# TFTLCD.net
KiCad netlist of a schematic drawn in EAGLE
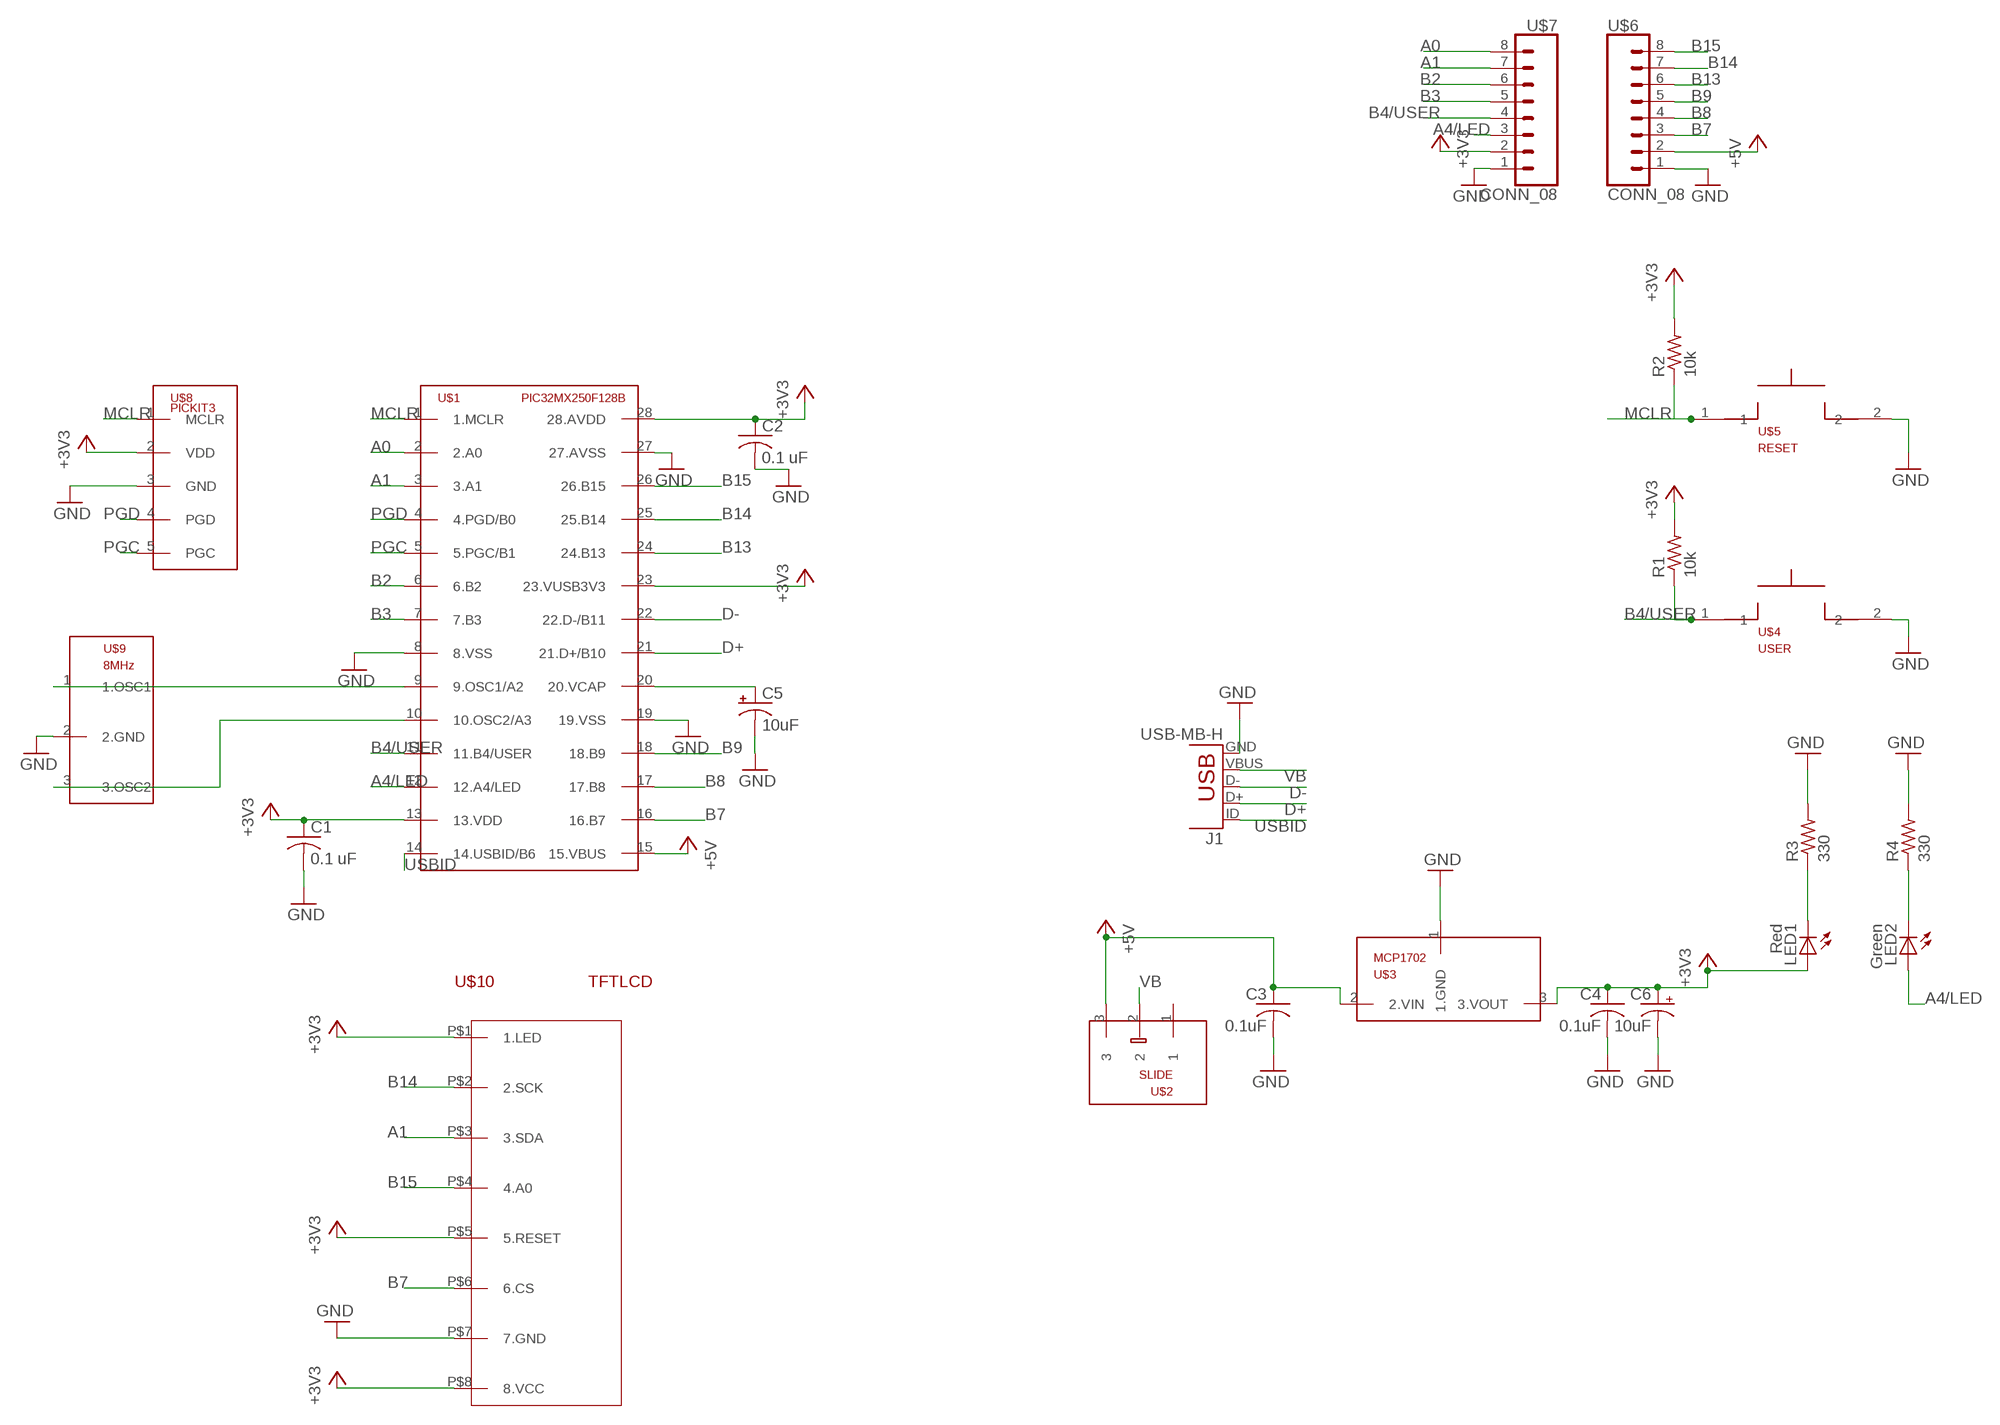
[diagram p0: schematic, sheet 1]

(export (version "E")
  (design (tool "Eeschema 10.0.6"))
  (components
    (comp (ref "C1")
      (value "0.1 uF")
      (footprint "eagle-import:C025-025X050")
      (libsource (lib "eagle-import") (part "C-US025-025X050"))
    )
    (comp (ref "C2")
      (value "0.1 uF")
      (footprint "eagle-import:C025-025X050")
      (libsource (lib "eagle-import") (part "C-US025-025X050"))
    )
    (comp (ref "C3")
      (value "0.1uF")
      (footprint "eagle-import:C025-025X050")
      (libsource (lib "eagle-import") (part "C-US025-025X050"))
    )
    (comp (ref "C4")
      (value "0.1uF")
      (footprint "eagle-import:C025-025X050")
      (libsource (lib "eagle-import") (part "C-US025-025X050"))
    )
    (comp (ref "C5")
      (value "10uF")
      (footprint "eagle-import:B45181B")
      (libsource (lib "eagle-import") (part "CPOL-USB45181B"))
    )
    (comp (ref "C6")
      (value "10uF")
      (footprint "eagle-import:B45181B")
      (libsource (lib "eagle-import") (part "CPOL-USB45181B"))
    )
    (comp (ref "J1")
      (value "USB-MB-H")
      (footprint "eagle-import:USB-MB-H")
      (libsource (lib "eagle-import") (part "USB-MB-H"))
    )
    (comp (ref "LED1")
      (value "Red")
      (footprint "eagle-import:LED3MM")
      (libsource (lib "eagle-import") (part "LED3MM"))
    )
    (comp (ref "LED2")
      (value "Green")
      (footprint "eagle-import:LED3MM")
      (libsource (lib "eagle-import") (part "LED3MM"))
    )
    (comp (ref "R1")
      (value "10k")
      (footprint "eagle-import:0207_10")
      (libsource (lib "eagle-import") (part "R-US_0207/10"))
    )
    (comp (ref "R2")
      (value "10k")
      (footprint "eagle-import:0207_10")
      (libsource (lib "eagle-import") (part "R-US_0207/10"))
    )
    (comp (ref "R3")
      (value "330")
      (footprint "eagle-import:0207_10")
      (libsource (lib "eagle-import") (part "R-US_0207/10"))
    )
    (comp (ref "R4")
      (value "330")
      (footprint "eagle-import:0207_10")
      (libsource (lib "eagle-import") (part "R-US_0207/10"))
    )
    (comp (ref "U$1")
      (value "PIC32MX250F128B")
      (footprint "eagle-import:DIL28-3")
      (libsource (lib "eagle-import") (part "PIC32MX250F128B"))
    )
    (comp (ref "U$2")
      (value "SLIDE")
      (footprint "eagle-import:SLIDE")
      (libsource (lib "eagle-import") (part "SLIDE"))
    )
    (comp (ref "U$3")
      (value "MCP1702")
      (footprint "eagle-import:TO92")
      (libsource (lib "eagle-import") (part "MCP1702"))
    )
    (comp (ref "U$4")
      (value "USER")
      (footprint "eagle-import:PB")
      (libsource (lib "eagle-import") (part "PB"))
    )
    (comp (ref "U$5")
      (value "RESET")
      (footprint "eagle-import:PB")
      (libsource (lib "eagle-import") (part "PB"))
    )
    (comp (ref "U$6")
      (value "CONN_08")
      (footprint "eagle-import:1X08")
      (libsource (lib "eagle-import") (part "CONN_08"))
    )
    (comp (ref "U$7")
      (value "CONN_08")
      (footprint "eagle-import:1X08")
      (libsource (lib "eagle-import") (part "CONN_08"))
    )
    (comp (ref "U$8")
      (value "PICKIT3")
      (footprint "eagle-import:1X05")
      (libsource (lib "eagle-import") (part "PICKIT3"))
    )
    (comp (ref "U$9")
      (value "8MHz")
      (footprint "eagle-import:OSC")
      (libsource (lib "eagle-import") (part "OSC"))
    )
    (comp (ref "U$10")
      (value "TFTLCD")
      (footprint "eagle-import:TFTLCD")
      (libsource (lib "eagle-import") (part "TFTLCD"))
    )
  )
  (nets
    (net (code "1") (name "+3V3") (class "Default")
      (node (ref "C1") (pin "1") (pinfunction "1_1") (pintype "passive"))
      (node (ref "C2") (pin "1") (pinfunction "1_1") (pintype "passive"))
      (node (ref "C4") (pin "1") (pinfunction "1_1") (pintype "passive"))
      (node (ref "C6") (pin "+") (pinfunction "+_+") (pintype "passive"))
      (node (ref "LED1") (pin "A") (pinfunction "A_A") (pintype "passive"))
      (node (ref "R1") (pin "2") (pinfunction "2_2") (pintype "passive"))
      (node (ref "R2") (pin "2") (pinfunction "2_2") (pintype "passive"))
      (node (ref "U$1") (pin "13") (pinfunction "13.VDD_13") (pintype "bidirectional"))
      (node (ref "U$1") (pin "23") (pinfunction "23.VUSB3V3_23") (pintype "bidirectional"))
      (node (ref "U$1") (pin "28") (pinfunction "28.AVDD_28") (pintype "bidirectional"))
      (node (ref "U$10") (pin "P$1") (pinfunction "1.LED_P$1") (pintype "bidirectional"))
      (node (ref "U$10") (pin "P$5") (pinfunction "5.RESET_P$5") (pintype "bidirectional"))
      (node (ref "U$10") (pin "P$8") (pinfunction "8.VCC_P$8") (pintype "bidirectional"))
      (node (ref "U$3") (pin "3") (pinfunction "3.VOUT_3") (pintype "bidirectional"))
      (node (ref "U$7") (pin "2") (pinfunction "2_2") (pintype "passive"))
      (node (ref "U$8") (pin "2") (pinfunction "VDD_2") (pintype "bidirectional"))
    )
    (net (code "2") (name "+5V") (class "Default")
      (node (ref "C3") (pin "1") (pinfunction "1_1") (pintype "passive"))
      (node (ref "U$1") (pin "15") (pinfunction "15.VBUS_15") (pintype "bidirectional"))
      (node (ref "U$2") (pin "3") (pinfunction "3_3") (pintype "bidirectional"))
      (node (ref "U$3") (pin "2") (pinfunction "2.VIN_2") (pintype "bidirectional"))
      (node (ref "U$6") (pin "2") (pinfunction "2_2") (pintype "passive"))
    )
    (net (code "3") (name "/A0") (class "Default")
      (node (ref "U$1") (pin "2") (pinfunction "2.A0_2") (pintype "bidirectional"))
      (node (ref "U$7") (pin "8") (pinfunction "8_8") (pintype "passive"))
    )
    (net (code "4") (name "/A1") (class "Default")
      (node (ref "U$1") (pin "3") (pinfunction "3.A1_3") (pintype "bidirectional"))
      (node (ref "U$10") (pin "P$3") (pinfunction "3.SDA_P$3") (pintype "bidirectional"))
      (node (ref "U$7") (pin "7") (pinfunction "7_7") (pintype "passive"))
    )
    (net (code "5") (name "/A4{slash}LED") (class "Default")
      (node (ref "LED2") (pin "A") (pinfunction "A_A") (pintype "passive"))
      (node (ref "U$1") (pin "12") (pinfunction "12.A4/LED_12") (pintype "bidirectional"))
      (node (ref "U$7") (pin "3") (pinfunction "3_3") (pintype "passive"))
    )
    (net (code "6") (name "/B2") (class "Default")
      (node (ref "U$1") (pin "6") (pinfunction "6.B2_6") (pintype "bidirectional"))
      (node (ref "U$7") (pin "6") (pinfunction "6_6") (pintype "passive"))
    )
    (net (code "7") (name "/B3") (class "Default")
      (node (ref "U$1") (pin "7") (pinfunction "7.B3_7") (pintype "bidirectional"))
      (node (ref "U$7") (pin "5") (pinfunction "5_5") (pintype "passive"))
    )
    (net (code "8") (name "/B4{slash}USER") (class "Default")
      (node (ref "R1") (pin "1") (pinfunction "1_1") (pintype "passive"))
      (node (ref "U$1") (pin "11") (pinfunction "11.B4/USER_11") (pintype "bidirectional"))
      (node (ref "U$4") (pin "1") (pinfunction "1_1") (pintype "bidirectional"))
      (node (ref "U$7") (pin "4") (pinfunction "4_4") (pintype "passive"))
    )
    (net (code "9") (name "/B7") (class "Default")
      (node (ref "U$1") (pin "16") (pinfunction "16.B7_16") (pintype "bidirectional"))
      (node (ref "U$10") (pin "P$6") (pinfunction "6.CS_P$6") (pintype "bidirectional"))
      (node (ref "U$6") (pin "3") (pinfunction "3_3") (pintype "passive"))
    )
    (net (code "10") (name "/B8") (class "Default")
      (node (ref "U$1") (pin "17") (pinfunction "17.B8_17") (pintype "bidirectional"))
      (node (ref "U$6") (pin "4") (pinfunction "4_4") (pintype "passive"))
    )
    (net (code "11") (name "/B9") (class "Default")
      (node (ref "U$1") (pin "18") (pinfunction "18.B9_18") (pintype "bidirectional"))
      (node (ref "U$6") (pin "5") (pinfunction "5_5") (pintype "passive"))
    )
    (net (code "12") (name "/B13") (class "Default")
      (node (ref "U$1") (pin "24") (pinfunction "24.B13_24") (pintype "bidirectional"))
      (node (ref "U$6") (pin "6") (pinfunction "6_6") (pintype "passive"))
    )
    (net (code "13") (name "/B14") (class "Default")
      (node (ref "U$1") (pin "25") (pinfunction "25.B14_25") (pintype "bidirectional"))
      (node (ref "U$10") (pin "P$2") (pinfunction "2.SCK_P$2") (pintype "bidirectional"))
      (node (ref "U$6") (pin "7") (pinfunction "7_7") (pintype "passive"))
    )
    (net (code "14") (name "/B15") (class "Default")
      (node (ref "U$1") (pin "26") (pinfunction "26.B15_26") (pintype "bidirectional"))
      (node (ref "U$10") (pin "P$4") (pinfunction "4.A0_P$4") (pintype "bidirectional"))
      (node (ref "U$6") (pin "8") (pinfunction "8_8") (pintype "passive"))
    )
    (net (code "15") (name "/D+") (class "Default")
      (node (ref "J1") (pin "D+") (pinfunction "D+_D+") (pintype "bidirectional"))
      (node (ref "U$1") (pin "21") (pinfunction "21.D+/B10_21") (pintype "bidirectional"))
    )
    (net (code "16") (name "/D-") (class "Default")
      (node (ref "J1") (pin "D-") (pinfunction "D-_D-") (pintype "bidirectional"))
      (node (ref "U$1") (pin "22") (pinfunction "22.D-/B11_22") (pintype "bidirectional"))
    )
    (net (code "17") (name "/MCLR") (class "Default")
      (node (ref "R2") (pin "1") (pinfunction "1_1") (pintype "passive"))
      (node (ref "U$1") (pin "1") (pinfunction "1.MCLR_1") (pintype "bidirectional"))
      (node (ref "U$5") (pin "1") (pinfunction "1_1") (pintype "bidirectional"))
      (node (ref "U$8") (pin "1") (pinfunction "MCLR_1") (pintype "bidirectional"))
    )
    (net (code "18") (name "/PGC") (class "Default")
      (node (ref "U$1") (pin "5") (pinfunction "5.PGC/B1_5") (pintype "bidirectional"))
      (node (ref "U$8") (pin "5") (pinfunction "PGC_5") (pintype "bidirectional"))
    )
    (net (code "19") (name "/PGD") (class "Default")
      (node (ref "U$1") (pin "4") (pinfunction "4.PGD/B0_4") (pintype "bidirectional"))
      (node (ref "U$8") (pin "4") (pinfunction "PGD_4") (pintype "bidirectional"))
    )
    (net (code "20") (name "/USBID") (class "Default")
      (node (ref "J1") (pin "ID") (pinfunction "ID_ID") (pintype "bidirectional"))
      (node (ref "U$1") (pin "14") (pinfunction "14.USBID/B6_14") (pintype "bidirectional"))
    )
    (net (code "21") (name "/VB") (class "Default")
      (node (ref "J1") (pin "VBUS") (pinfunction "VBUS_VBUS") (pintype "bidirectional"))
      (node (ref "U$2") (pin "2") (pinfunction "2_2") (pintype "bidirectional"))
    )
    (net (code "22") (name "GND") (class "Default")
      (node (ref "C1") (pin "2") (pinfunction "2_2") (pintype "passive"))
      (node (ref "C2") (pin "2") (pinfunction "2_2") (pintype "passive"))
      (node (ref "C3") (pin "2") (pinfunction "2_2") (pintype "passive"))
      (node (ref "C4") (pin "2") (pinfunction "2_2") (pintype "passive"))
      (node (ref "C5") (pin "-") (pinfunction "-_-") (pintype "passive"))
      (node (ref "C6") (pin "-") (pinfunction "-_-") (pintype "passive"))
      (node (ref "J1") (pin "GND") (pinfunction "GND_GND") (pintype "bidirectional"))
      (node (ref "R3") (pin "2") (pinfunction "2_2") (pintype "passive"))
      (node (ref "R4") (pin "2") (pinfunction "2_2") (pintype "passive"))
      (node (ref "U$1") (pin "19") (pinfunction "19.VSS_19") (pintype "bidirectional"))
      (node (ref "U$1") (pin "27") (pinfunction "27.AVSS_27") (pintype "bidirectional"))
      (node (ref "U$1") (pin "8") (pinfunction "8.VSS_8") (pintype "bidirectional"))
      (node (ref "U$10") (pin "P$7") (pinfunction "7.GND_P$7") (pintype "bidirectional"))
      (node (ref "U$3") (pin "1") (pinfunction "1.GND_1") (pintype "bidirectional"))
      (node (ref "U$4") (pin "2") (pinfunction "2_2") (pintype "bidirectional"))
      (node (ref "U$5") (pin "2") (pinfunction "2_2") (pintype "bidirectional"))
      (node (ref "U$6") (pin "1") (pinfunction "1_1") (pintype "passive"))
      (node (ref "U$7") (pin "1") (pinfunction "1_1") (pintype "passive"))
      (node (ref "U$8") (pin "3") (pinfunction "GND_3") (pintype "bidirectional"))
      (node (ref "U$9") (pin "2") (pinfunction "2.GND_2") (pintype "bidirectional"))
    )
    (net (code "23") (name "Net-(LED1-C)") (class "Default")
      (node (ref "LED1") (pin "K") (pinfunction "C_K") (pintype "passive"))
      (node (ref "R3") (pin "1") (pinfunction "1_1") (pintype "passive"))
    )
    (net (code "24") (name "Net-(LED2-C)") (class "Default")
      (node (ref "LED2") (pin "K") (pinfunction "C_K") (pintype "passive"))
      (node (ref "R4") (pin "1") (pinfunction "1_1") (pintype "passive"))
    )
    (net (code "25") (name "Net-(U$1-9.OSC1{slash}A2)") (class "Default")
      (node (ref "U$1") (pin "9") (pinfunction "9.OSC1/A2_9") (pintype "bidirectional"))
      (node (ref "U$9") (pin "1") (pinfunction "1.OSC1_1") (pintype "bidirectional"))
    )
    (net (code "26") (name "Net-(U$1-10.OSC2{slash}A3)") (class "Default")
      (node (ref "U$1") (pin "10") (pinfunction "10.OSC2/A3_10") (pintype "bidirectional"))
      (node (ref "U$9") (pin "3") (pinfunction "3.OSC2_3") (pintype "bidirectional"))
    )
    (net (code "27") (name "Net-(U$1-20.VCAP)") (class "Default")
      (node (ref "C5") (pin "+") (pinfunction "+_+") (pintype "passive"))
      (node (ref "U$1") (pin "20") (pinfunction "20.VCAP_20") (pintype "bidirectional"))
    )
    (net (code "28") (name "unconnected-(U$2-Pad1)") (class "Default")
      (node (ref "U$2") (pin "1") (pinfunction "1_1") (pintype "bidirectional"))
    )
  )
)
